# NTC.net
KiCad netlist of a schematic drawn in Altium Designer
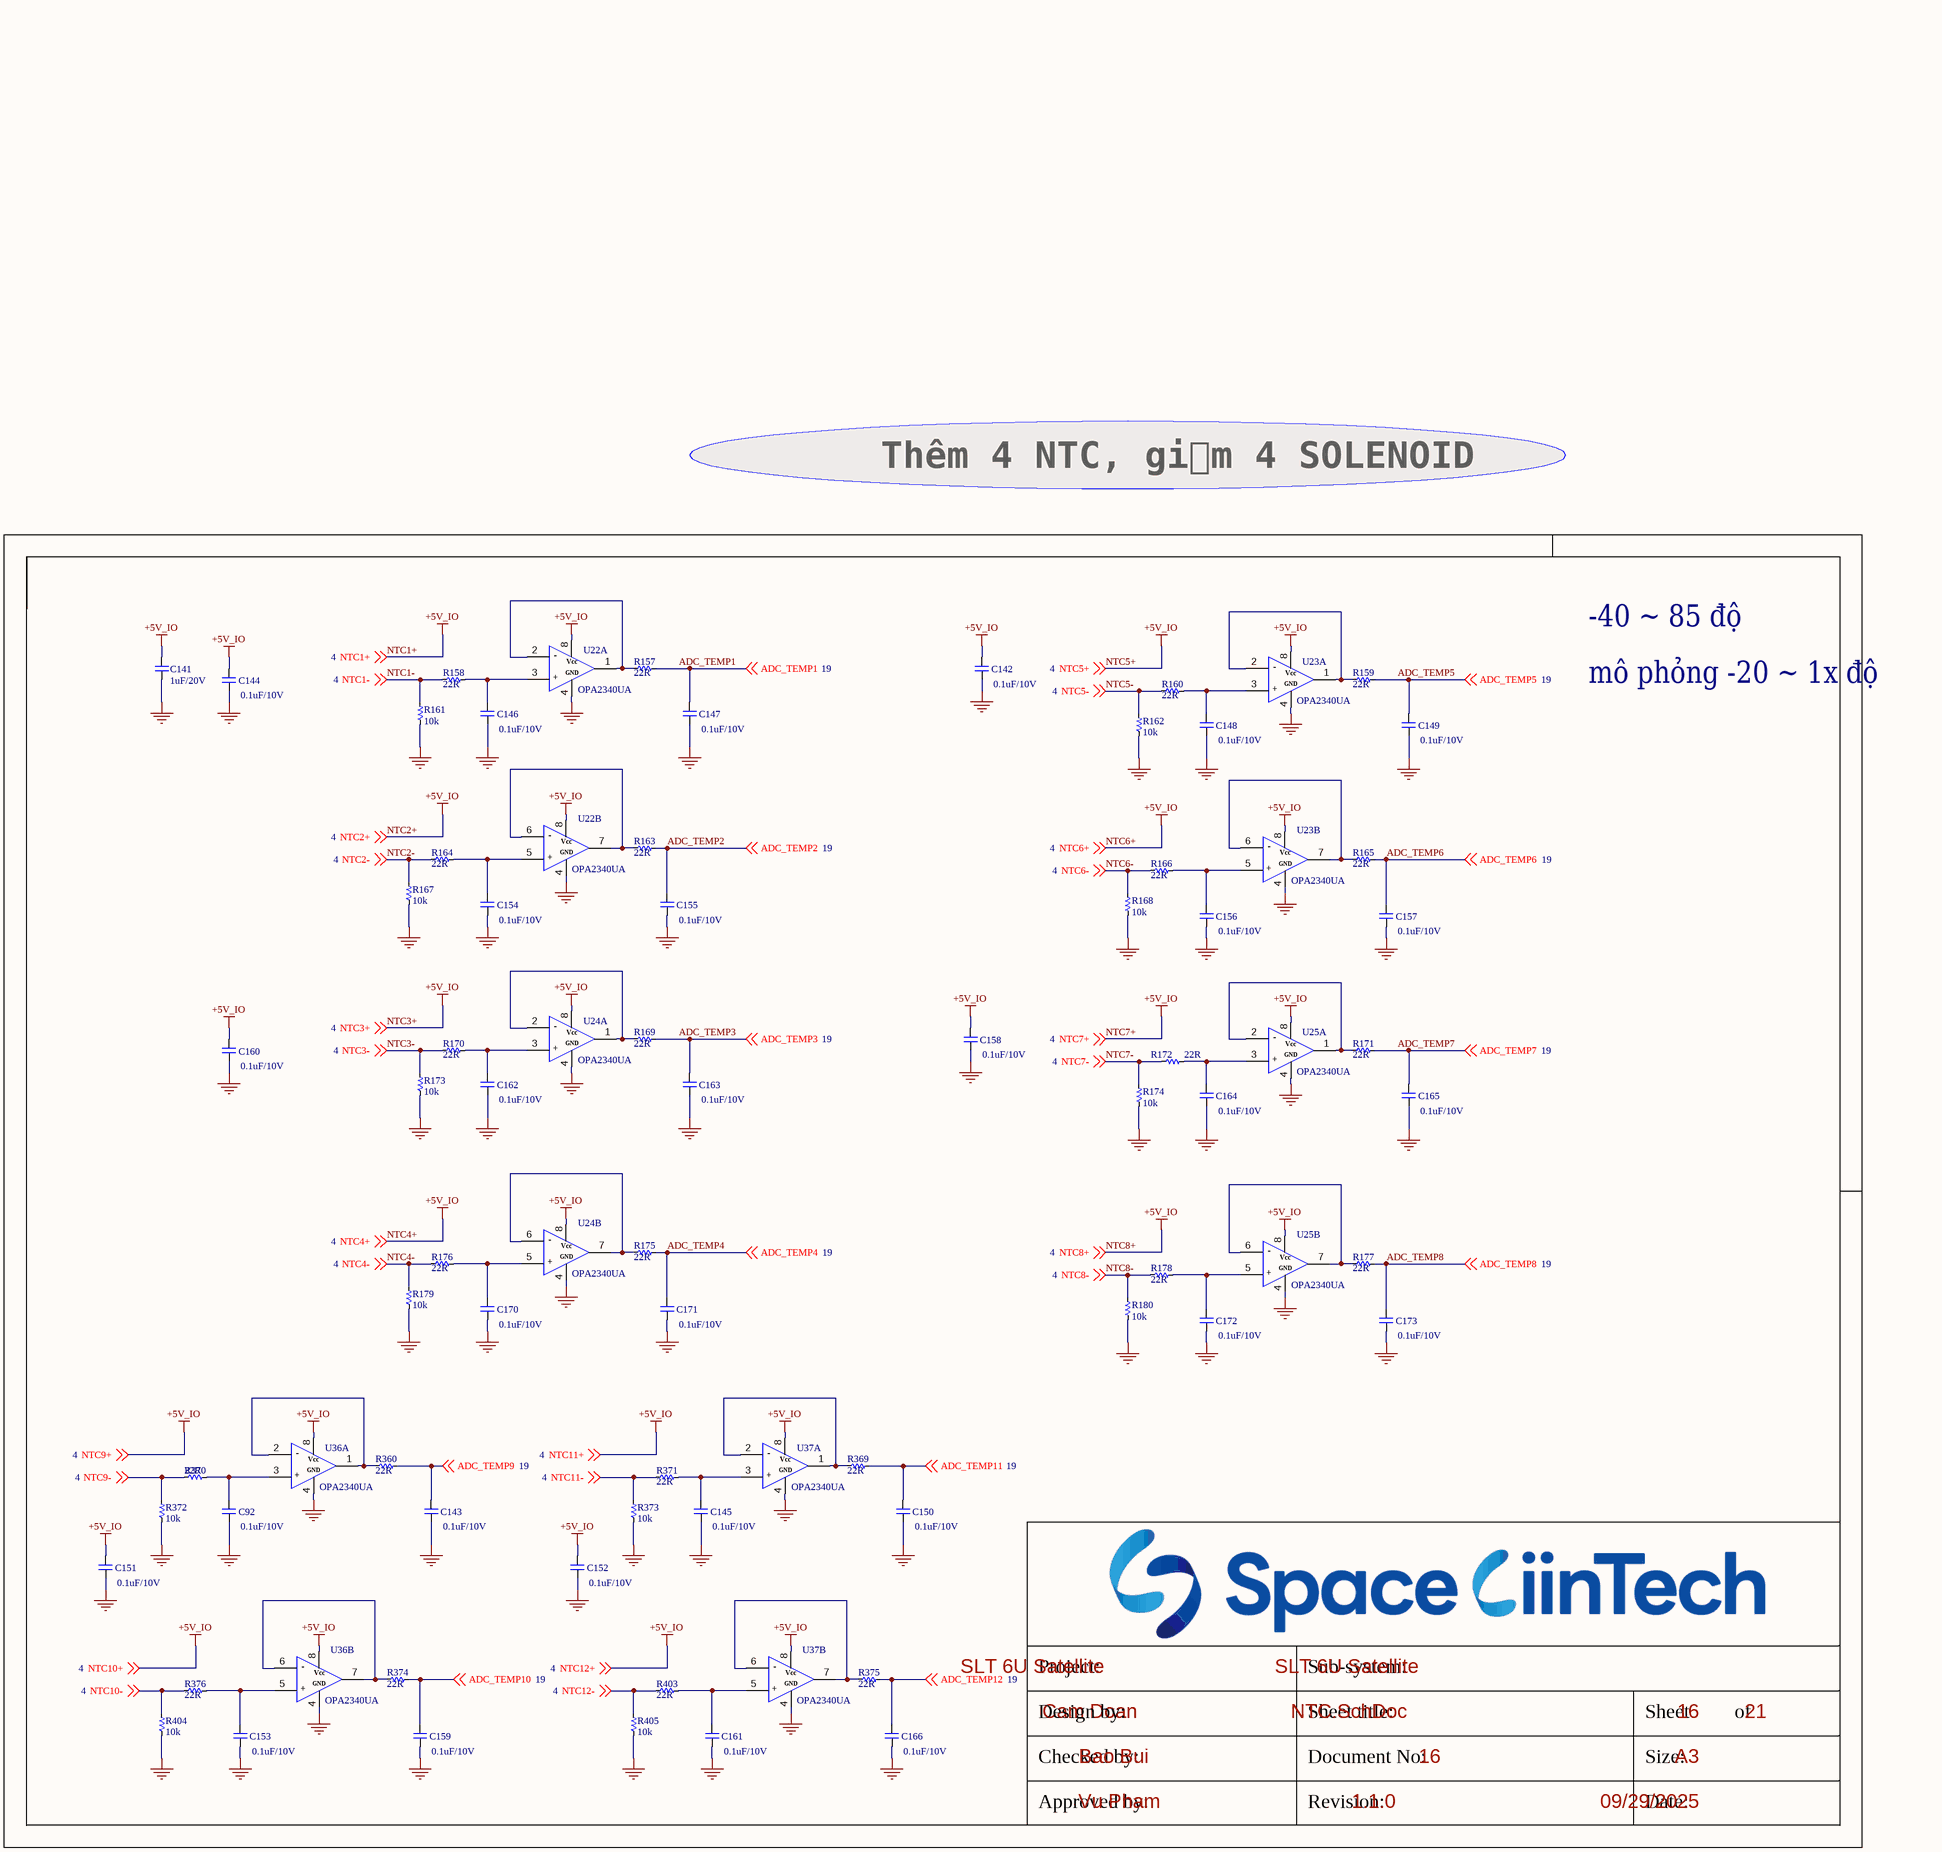
[diagram p0: NTC.SchDoc]

(export (version "E")
  (design (tool "Eeschema 10.0.6"))
  (components
    (comp (ref "C92")
      (value "0.1uF/10V")
      (footprint "CAP_C_1005X60")
      (description "CAP CHIP")
      (libsource (lib "LABLIB") (part "_CAP_C_2"))
    )
    (comp (ref "C141")
      (value "1uF/20V")
      (footprint "CAP_C_1005X60")
      (description "CAP CHIP")
      (libsource (lib "LABLIB") (part "_CAP_C_2"))
    )
    (comp (ref "C142")
      (value "0.1uF/10V")
      (footprint "CAP_C_1005X60")
      (description "CAP CHIP")
      (libsource (lib "LABLIB") (part "_CAP_C_2"))
    )
    (comp (ref "C143")
      (value "0.1uF/10V")
      (footprint "CAP_C_1005X60")
      (description "CAP CHIP")
      (libsource (lib "LABLIB") (part "_CAP_C_2"))
    )
    (comp (ref "C144")
      (value "0.1uF/10V")
      (footprint "CAP_C_1005X60")
      (description "CAP CHIP")
      (libsource (lib "LABLIB") (part "_CAP_C_2"))
    )
    (comp (ref "C145")
      (value "0.1uF/10V")
      (footprint "CAP_C_1005X60")
      (description "CAP CHIP")
      (libsource (lib "LABLIB") (part "_CAP_C_2"))
    )
    (comp (ref "C146")
      (value "0.1uF/10V")
      (footprint "CAP_C_1005X60")
      (description "CAP CHIP")
      (libsource (lib "LABLIB") (part "_CAP_C_2"))
    )
    (comp (ref "C147")
      (value "0.1uF/10V")
      (footprint "CAP_C_1005X60")
      (description "CAP CHIP")
      (libsource (lib "LABLIB") (part "_CAP_C_2"))
    )
    (comp (ref "C148")
      (value "0.1uF/10V")
      (footprint "CAP_C_1005X60")
      (description "CAP CHIP")
      (libsource (lib "LABLIB") (part "_CAP_C_2"))
    )
    (comp (ref "C149")
      (value "0.1uF/10V")
      (footprint "CAP_C_1005X60")
      (description "CAP CHIP")
      (libsource (lib "LABLIB") (part "_CAP_C_2"))
    )
    (comp (ref "C150")
      (value "0.1uF/10V")
      (footprint "CAP_C_1005X60")
      (description "CAP CHIP")
      (libsource (lib "LABLIB") (part "_CAP_C_2"))
    )
    (comp (ref "C151")
      (value "0.1uF/10V")
      (footprint "CAP_C_1005X60")
      (description "CAP CHIP")
      (libsource (lib "LABLIB") (part "_CAP_C_2"))
    )
    (comp (ref "C152")
      (value "0.1uF/10V")
      (footprint "CAP_C_1005X60")
      (description "CAP CHIP")
      (libsource (lib "LABLIB") (part "_CAP_C_2"))
    )
    (comp (ref "C153")
      (value "0.1uF/10V")
      (footprint "CAP_C_1005X60")
      (description "CAP CHIP")
      (libsource (lib "LABLIB") (part "_CAP_C_2"))
    )
    (comp (ref "C154")
      (value "0.1uF/10V")
      (footprint "CAP_C_1005X60")
      (description "CAP CHIP")
      (libsource (lib "LABLIB") (part "_CAP_C_2"))
    )
    (comp (ref "C155")
      (value "0.1uF/10V")
      (footprint "CAP_C_1005X60")
      (description "CAP CHIP")
      (libsource (lib "LABLIB") (part "_CAP_C_2"))
    )
    (comp (ref "C156")
      (value "0.1uF/10V")
      (footprint "CAP_C_1005X60")
      (description "CAP CHIP")
      (libsource (lib "LABLIB") (part "_CAP_C_2"))
    )
    (comp (ref "C157")
      (value "0.1uF/10V")
      (footprint "CAP_C_1005X60")
      (description "CAP CHIP")
      (libsource (lib "LABLIB") (part "_CAP_C_2"))
    )
    (comp (ref "C158")
      (value "0.1uF/10V")
      (footprint "CAP_C_1005X60")
      (description "CAP CHIP")
      (libsource (lib "LABLIB") (part "_CAP_C_2"))
    )
    (comp (ref "C159")
      (value "0.1uF/10V")
      (footprint "CAP_C_1005X60")
      (description "CAP CHIP")
      (libsource (lib "LABLIB") (part "_CAP_C_2"))
    )
    (comp (ref "C160")
      (value "0.1uF/10V")
      (footprint "CAP_C_1005X60")
      (description "CAP CHIP")
      (libsource (lib "LABLIB") (part "_CAP_C_2"))
    )
    (comp (ref "C161")
      (value "0.1uF/10V")
      (footprint "CAP_C_1005X60")
      (description "CAP CHIP")
      (libsource (lib "LABLIB") (part "_CAP_C_2"))
    )
    (comp (ref "C162")
      (value "0.1uF/10V")
      (footprint "CAP_C_1005X60")
      (description "CAP CHIP")
      (libsource (lib "LABLIB") (part "_CAP_C_2"))
    )
    (comp (ref "C163")
      (value "0.1uF/10V")
      (footprint "CAP_C_1005X60")
      (description "CAP CHIP")
      (libsource (lib "LABLIB") (part "_CAP_C_2"))
    )
    (comp (ref "C164")
      (value "0.1uF/10V")
      (footprint "CAP_C_1005X60")
      (description "CAP CHIP")
      (libsource (lib "LABLIB") (part "_CAP_C_2"))
    )
    (comp (ref "C165")
      (value "0.1uF/10V")
      (footprint "CAP_C_1005X60")
      (description "CAP CHIP")
      (libsource (lib "LABLIB") (part "_CAP_C_2"))
    )
    (comp (ref "C166")
      (value "0.1uF/10V")
      (footprint "CAP_C_1005X60")
      (description "CAP CHIP")
      (libsource (lib "LABLIB") (part "_CAP_C_2"))
    )
    (comp (ref "C170")
      (value "0.1uF/10V")
      (footprint "CAP_C_1005X60")
      (description "CAP CHIP")
      (libsource (lib "LABLIB") (part "_CAP_C_2"))
    )
    (comp (ref "C171")
      (value "0.1uF/10V")
      (footprint "CAP_C_1005X60")
      (description "CAP CHIP")
      (libsource (lib "LABLIB") (part "_CAP_C_2"))
    )
    (comp (ref "C172")
      (value "0.1uF/10V")
      (footprint "CAP_C_1005X60")
      (description "CAP CHIP")
      (libsource (lib "LABLIB") (part "_CAP_C_2"))
    )
    (comp (ref "C173")
      (value "0.1uF/10V")
      (footprint "CAP_C_1005X60")
      (description "CAP CHIP")
      (libsource (lib "LABLIB") (part "_CAP_C_2"))
    )
    (comp (ref "R157")
      (value "22R")
      (footprint "RES_C_1005X40")
      (description "RES")
      (libsource (lib "LABLIB") (part "_RES_B_2"))
    )
    (comp (ref "R158")
      (value "22R")
      (footprint "RES_C_1005X40")
      (description "RES")
      (libsource (lib "LABLIB") (part "_RES_B_2"))
    )
    (comp (ref "R159")
      (value "22R")
      (footprint "RES_C_1005X40")
      (description "RES")
      (libsource (lib "LABLIB") (part "_RES_B_2"))
    )
    (comp (ref "R160")
      (value "22R")
      (footprint "RES_C_1005X40")
      (description "RES")
      (libsource (lib "LABLIB") (part "_RES_B_2"))
    )
    (comp (ref "R161")
      (value "10k")
      (footprint "RES_C_1005X40")
      (description "RES")
      (libsource (lib "LABLIB") (part "_RES_B_2"))
    )
    (comp (ref "R162")
      (value "10k")
      (footprint "RES_C_1005X40")
      (description "RES")
      (libsource (lib "LABLIB") (part "_RES_B_2"))
    )
    (comp (ref "R163")
      (value "22R")
      (footprint "RES_C_1005X40")
      (description "RES")
      (libsource (lib "LABLIB") (part "_RES_B_2"))
    )
    (comp (ref "R164")
      (value "22R")
      (footprint "RES_C_1005X40")
      (description "RES")
      (libsource (lib "LABLIB") (part "_RES_B_2"))
    )
    (comp (ref "R165")
      (value "22R")
      (footprint "RES_C_1005X40")
      (description "RES")
      (libsource (lib "LABLIB") (part "_RES_B_2"))
    )
    (comp (ref "R166")
      (value "22R")
      (footprint "RES_C_1005X40")
      (description "RES")
      (libsource (lib "LABLIB") (part "_RES_B_2"))
    )
    (comp (ref "R167")
      (value "10k")
      (footprint "RES_C_1005X40")
      (description "RES")
      (libsource (lib "LABLIB") (part "_RES_B_2"))
    )
    (comp (ref "R168")
      (value "10k")
      (footprint "RES_C_1005X40")
      (description "RES")
      (libsource (lib "LABLIB") (part "_RES_B_2"))
    )
    (comp (ref "R169")
      (value "22R")
      (footprint "RES_C_1005X40")
      (description "RES")
      (libsource (lib "LABLIB") (part "_RES_B_2"))
    )
    (comp (ref "R170")
      (value "22R")
      (footprint "RES_C_1005X40")
      (description "RES")
      (libsource (lib "LABLIB") (part "_RES_B_2"))
    )
    (comp (ref "R171")
      (value "22R")
      (footprint "RES_C_1005X40")
      (description "RES")
      (libsource (lib "LABLIB") (part "_RES_B_2"))
    )
    (comp (ref "R172")
      (value "22R")
      (footprint "RES_C_1005X40")
      (description "RES")
      (libsource (lib "LABLIB") (part "_RES_B_2"))
    )
    (comp (ref "R173")
      (value "10k")
      (footprint "RES_C_1005X40")
      (description "RES")
      (libsource (lib "LABLIB") (part "_RES_B_2"))
    )
    (comp (ref "R174")
      (value "10k")
      (footprint "RES_C_1005X40")
      (description "RES")
      (libsource (lib "LABLIB") (part "_RES_B_2"))
    )
    (comp (ref "R175")
      (value "22R")
      (footprint "RES_C_1005X40")
      (description "RES")
      (libsource (lib "LABLIB") (part "_RES_B_2"))
    )
    (comp (ref "R176")
      (value "22R")
      (footprint "RES_C_1005X40")
      (description "RES")
      (libsource (lib "LABLIB") (part "_RES_B_2"))
    )
    (comp (ref "R177")
      (value "22R")
      (footprint "RES_C_1005X40")
      (description "RES")
      (libsource (lib "LABLIB") (part "_RES_B_2"))
    )
    (comp (ref "R178")
      (value "22R")
      (footprint "RES_C_1005X40")
      (description "RES")
      (libsource (lib "LABLIB") (part "_RES_B_2"))
    )
    (comp (ref "R179")
      (value "10k")
      (footprint "RES_C_1005X40")
      (description "RES")
      (libsource (lib "LABLIB") (part "_RES_B_2"))
    )
    (comp (ref "R180")
      (value "10k")
      (footprint "RES_C_1005X40")
      (description "RES")
      (libsource (lib "LABLIB") (part "_RES_B_2"))
    )
    (comp (ref "R360")
      (value "22R")
      (footprint "RES_C_1005X40")
      (description "RES")
      (libsource (lib "LABLIB") (part "_RES_B_2"))
    )
    (comp (ref "R369")
      (value "22R")
      (footprint "RES_C_1005X40")
      (description "RES")
      (libsource (lib "LABLIB") (part "_RES_B_2"))
    )
    (comp (ref "R370")
      (value "22R")
      (footprint "RES_C_1005X40")
      (description "RES")
      (libsource (lib "LABLIB") (part "_RES_B_2"))
    )
    (comp (ref "R371")
      (value "22R")
      (footprint "RES_C_1005X40")
      (description "RES")
      (libsource (lib "LABLIB") (part "_RES_B_2"))
    )
    (comp (ref "R372")
      (value "10k")
      (footprint "RES_C_1005X40")
      (description "RES")
      (libsource (lib "LABLIB") (part "_RES_B_2"))
    )
    (comp (ref "R373")
      (value "10k")
      (footprint "RES_C_1005X40")
      (description "RES")
      (libsource (lib "LABLIB") (part "_RES_B_2"))
    )
    (comp (ref "R374")
      (value "22R")
      (footprint "RES_C_1005X40")
      (description "RES")
      (libsource (lib "LABLIB") (part "_RES_B_2"))
    )
    (comp (ref "R375")
      (value "22R")
      (footprint "RES_C_1005X40")
      (description "RES")
      (libsource (lib "LABLIB") (part "_RES_B_2"))
    )
    (comp (ref "R376")
      (value "22R")
      (footprint "RES_C_1005X40")
      (description "RES")
      (libsource (lib "LABLIB") (part "_RES_B_2"))
    )
    (comp (ref "R403")
      (value "22R")
      (footprint "RES_C_1005X40")
      (description "RES")
      (libsource (lib "LABLIB") (part "_RES_B_2"))
    )
    (comp (ref "R404")
      (value "10k")
      (footprint "RES_C_1005X40")
      (description "RES")
      (libsource (lib "LABLIB") (part "_RES_B_2"))
    )
    (comp (ref "R405")
      (value "10k")
      (footprint "RES_C_1005X40")
      (description "RES")
      (libsource (lib "LABLIB") (part "_RES_B_2"))
    )
    (comp (ref "U22")
      (value "OPA2340UA")
      (footprint "SOIC127P602X173-8N")
      (libsource (lib "EXP_HW_V3") (part "OPA2340UA"))
    )
    (comp (ref "U23")
      (value "OPA2340UA")
      (footprint "SOIC127P602X173-8N")
      (libsource (lib "EXP_HW_V3") (part "OPA2340UA"))
    )
    (comp (ref "U24")
      (value "OPA2340UA")
      (footprint "SOIC127P602X173-8N")
      (libsource (lib "EXP_HW_V3") (part "OPA2340UA"))
    )
    (comp (ref "U25")
      (value "OPA2340UA")
      (footprint "SOIC127P602X173-8N")
      (libsource (lib "EXP_HW_V3") (part "OPA2340UA"))
    )
    (comp (ref "U36")
      (value "OPA2340UA")
      (footprint "SOIC127P602X173-8N")
      (libsource (lib "EXP_HW_V3") (part "OPA2340UA"))
    )
    (comp (ref "U37")
      (value "OPA2340UA")
      (footprint "SOIC127P602X173-8N")
      (libsource (lib "EXP_HW_V3") (part "OPA2340UA"))
    )
  )
  (nets
    (net (code "1") (name "+5V_IO") (class "Default")
      (node (ref "C141") (pin "2") (pinfunction "2_2") (pintype "passive"))
      (node (ref "C142") (pin "2") (pinfunction "2_2") (pintype "passive"))
      (node (ref "C144") (pin "2") (pinfunction "2_2") (pintype "passive"))
      (node (ref "C151") (pin "2") (pinfunction "2_2") (pintype "passive"))
      (node (ref "C152") (pin "2") (pinfunction "2_2") (pintype "passive"))
      (node (ref "C158") (pin "2") (pinfunction "2_2") (pintype "passive"))
      (node (ref "C160") (pin "2") (pinfunction "2_2") (pintype "passive"))
      (node (ref "U22") (pin "8") (pinfunction "8_8") (pintype "passive"))
      (node (ref "U23") (pin "8") (pinfunction "8_8") (pintype "passive"))
      (node (ref "U24") (pin "8") (pinfunction "8_8") (pintype "passive"))
      (node (ref "U25") (pin "8") (pinfunction "8_8") (pintype "passive"))
      (node (ref "U36") (pin "8") (pinfunction "8_8") (pintype "passive"))
      (node (ref "U37") (pin "8") (pinfunction "8_8") (pintype "passive"))
    )
    (net (code "2") (name "ADC_TEMP1") (class "Default")
      (node (ref "C147") (pin "2") (pinfunction "2_2") (pintype "passive"))
      (node (ref "R157") (pin "2") (pinfunction "2_2") (pintype "passive"))
    )
    (net (code "3") (name "ADC_TEMP2") (class "Default")
      (node (ref "C155") (pin "2") (pinfunction "2_2") (pintype "passive"))
      (node (ref "R163") (pin "2") (pinfunction "2_2") (pintype "passive"))
    )
    (net (code "4") (name "ADC_TEMP3") (class "Default")
      (node (ref "C163") (pin "2") (pinfunction "2_2") (pintype "passive"))
      (node (ref "R169") (pin "2") (pinfunction "2_2") (pintype "passive"))
    )
    (net (code "5") (name "ADC_TEMP4") (class "Default")
      (node (ref "C171") (pin "2") (pinfunction "2_2") (pintype "passive"))
      (node (ref "R175") (pin "2") (pinfunction "2_2") (pintype "passive"))
    )
    (net (code "6") (name "ADC_TEMP5") (class "Default")
      (node (ref "C149") (pin "2") (pinfunction "2_2") (pintype "passive"))
      (node (ref "R159") (pin "2") (pinfunction "2_2") (pintype "passive"))
    )
    (net (code "7") (name "ADC_TEMP6") (class "Default")
      (node (ref "C157") (pin "2") (pinfunction "2_2") (pintype "passive"))
      (node (ref "R165") (pin "2") (pinfunction "2_2") (pintype "passive"))
    )
    (net (code "8") (name "ADC_TEMP7") (class "Default")
      (node (ref "C165") (pin "2") (pinfunction "2_2") (pintype "passive"))
      (node (ref "R171") (pin "2") (pinfunction "2_2") (pintype "passive"))
    )
    (net (code "9") (name "ADC_TEMP8") (class "Default")
      (node (ref "C173") (pin "2") (pinfunction "2_2") (pintype "passive"))
      (node (ref "R177") (pin "2") (pinfunction "2_2") (pintype "passive"))
    )
    (net (code "10") (name "ADC_TEMP9") (class "Default")
      (node (ref "C143") (pin "2") (pinfunction "2_2") (pintype "passive"))
      (node (ref "R360") (pin "2") (pinfunction "2_2") (pintype "passive"))
    )
    (net (code "11") (name "ADC_TEMP10") (class "Default")
      (node (ref "C159") (pin "2") (pinfunction "2_2") (pintype "passive"))
      (node (ref "R374") (pin "2") (pinfunction "2_2") (pintype "passive"))
    )
    (net (code "12") (name "ADC_TEMP11") (class "Default")
      (node (ref "C150") (pin "2") (pinfunction "2_2") (pintype "passive"))
      (node (ref "R369") (pin "2") (pinfunction "2_2") (pintype "passive"))
    )
    (net (code "13") (name "ADC_TEMP12") (class "Default")
      (node (ref "C166") (pin "2") (pinfunction "2_2") (pintype "passive"))
      (node (ref "R375") (pin "2") (pinfunction "2_2") (pintype "passive"))
    )
    (net (code "14") (name "GND") (class "Default")
      (node (ref "C141") (pin "1") (pinfunction "1_1") (pintype "passive"))
      (node (ref "C142") (pin "1") (pinfunction "1_1") (pintype "passive"))
      (node (ref "C143") (pin "1") (pinfunction "1_1") (pintype "passive"))
      (node (ref "C144") (pin "1") (pinfunction "1_1") (pintype "passive"))
      (node (ref "C145") (pin "1") (pinfunction "1_1") (pintype "passive"))
      (node (ref "C146") (pin "1") (pinfunction "1_1") (pintype "passive"))
      (node (ref "C147") (pin "1") (pinfunction "1_1") (pintype "passive"))
      (node (ref "C148") (pin "1") (pinfunction "1_1") (pintype "passive"))
      (node (ref "C149") (pin "1") (pinfunction "1_1") (pintype "passive"))
      (node (ref "C150") (pin "1") (pinfunction "1_1") (pintype "passive"))
      (node (ref "C151") (pin "1") (pinfunction "1_1") (pintype "passive"))
      (node (ref "C152") (pin "1") (pinfunction "1_1") (pintype "passive"))
      (node (ref "C153") (pin "1") (pinfunction "1_1") (pintype "passive"))
      (node (ref "C154") (pin "1") (pinfunction "1_1") (pintype "passive"))
      (node (ref "C155") (pin "1") (pinfunction "1_1") (pintype "passive"))
      (node (ref "C156") (pin "1") (pinfunction "1_1") (pintype "passive"))
      (node (ref "C157") (pin "1") (pinfunction "1_1") (pintype "passive"))
      (node (ref "C158") (pin "1") (pinfunction "1_1") (pintype "passive"))
      (node (ref "C159") (pin "1") (pinfunction "1_1") (pintype "passive"))
      (node (ref "C160") (pin "1") (pinfunction "1_1") (pintype "passive"))
      (node (ref "C161") (pin "1") (pinfunction "1_1") (pintype "passive"))
      (node (ref "C162") (pin "1") (pinfunction "1_1") (pintype "passive"))
      (node (ref "C163") (pin "1") (pinfunction "1_1") (pintype "passive"))
      (node (ref "C164") (pin "1") (pinfunction "1_1") (pintype "passive"))
      (node (ref "C165") (pin "1") (pinfunction "1_1") (pintype "passive"))
      (node (ref "C166") (pin "1") (pinfunction "1_1") (pintype "passive"))
      (node (ref "C170") (pin "1") (pinfunction "1_1") (pintype "passive"))
      (node (ref "C171") (pin "1") (pinfunction "1_1") (pintype "passive"))
      (node (ref "C172") (pin "1") (pinfunction "1_1") (pintype "passive"))
      (node (ref "C173") (pin "1") (pinfunction "1_1") (pintype "passive"))
      (node (ref "C92") (pin "1") (pinfunction "1_1") (pintype "passive"))
      (node (ref "R161") (pin "1") (pinfunction "1_1") (pintype "passive"))
      (node (ref "R162") (pin "1") (pinfunction "1_1") (pintype "passive"))
      (node (ref "R167") (pin "1") (pinfunction "1_1") (pintype "passive"))
      (node (ref "R168") (pin "1") (pinfunction "1_1") (pintype "passive"))
      (node (ref "R173") (pin "1") (pinfunction "1_1") (pintype "passive"))
      (node (ref "R174") (pin "1") (pinfunction "1_1") (pintype "passive"))
      (node (ref "R179") (pin "1") (pinfunction "1_1") (pintype "passive"))
      (node (ref "R180") (pin "1") (pinfunction "1_1") (pintype "passive"))
      (node (ref "R372") (pin "1") (pinfunction "1_1") (pintype "passive"))
      (node (ref "R373") (pin "1") (pinfunction "1_1") (pintype "passive"))
      (node (ref "R404") (pin "1") (pinfunction "1_1") (pintype "passive"))
      (node (ref "R405") (pin "1") (pinfunction "1_1") (pintype "passive"))
      (node (ref "U22") (pin "4") (pinfunction "4_4") (pintype "passive"))
      (node (ref "U23") (pin "4") (pinfunction "4_4") (pintype "passive"))
      (node (ref "U24") (pin "4") (pinfunction "4_4") (pintype "passive"))
      (node (ref "U25") (pin "4") (pinfunction "4_4") (pintype "passive"))
      (node (ref "U36") (pin "4") (pinfunction "4_4") (pintype "passive"))
      (node (ref "U37") (pin "4") (pinfunction "4_4") (pintype "passive"))
    )
    (net (code "15") (name "NTC1-") (class "Default")
      (node (ref "R158") (pin "1") (pinfunction "1_1") (pintype "passive"))
      (node (ref "R161") (pin "2") (pinfunction "2_2") (pintype "passive"))
    )
    (net (code "16") (name "NTC2-") (class "Default")
      (node (ref "R164") (pin "1") (pinfunction "1_1") (pintype "passive"))
      (node (ref "R167") (pin "2") (pinfunction "2_2") (pintype "passive"))
    )
    (net (code "17") (name "NTC3-") (class "Default")
      (node (ref "R170") (pin "1") (pinfunction "1_1") (pintype "passive"))
      (node (ref "R173") (pin "2") (pinfunction "2_2") (pintype "passive"))
    )
    (net (code "18") (name "NTC4-") (class "Default")
      (node (ref "R176") (pin "1") (pinfunction "1_1") (pintype "passive"))
      (node (ref "R179") (pin "2") (pinfunction "2_2") (pintype "passive"))
    )
    (net (code "19") (name "NTC5-") (class "Default")
      (node (ref "R160") (pin "1") (pinfunction "1_1") (pintype "passive"))
      (node (ref "R162") (pin "2") (pinfunction "2_2") (pintype "passive"))
    )
    (net (code "20") (name "NTC6-") (class "Default")
      (node (ref "R166") (pin "1") (pinfunction "1_1") (pintype "passive"))
      (node (ref "R168") (pin "2") (pinfunction "2_2") (pintype "passive"))
    )
    (net (code "21") (name "NTC7-") (class "Default")
      (node (ref "R172") (pin "1") (pinfunction "1_1") (pintype "passive"))
      (node (ref "R174") (pin "2") (pinfunction "2_2") (pintype "passive"))
    )
    (net (code "22") (name "NTC8-") (class "Default")
      (node (ref "R178") (pin "1") (pinfunction "1_1") (pintype "passive"))
      (node (ref "R180") (pin "2") (pinfunction "2_2") (pintype "passive"))
    )
    (net (code "23") (name "NTC9-") (class "Default")
      (node (ref "R370") (pin "1") (pinfunction "1_1") (pintype "passive"))
      (node (ref "R372") (pin "2") (pinfunction "2_2") (pintype "passive"))
    )
    (net (code "24") (name "NTC10-") (class "Default")
      (node (ref "R376") (pin "1") (pinfunction "1_1") (pintype "passive"))
      (node (ref "R404") (pin "2") (pinfunction "2_2") (pintype "passive"))
    )
    (net (code "25") (name "NTC11-") (class "Default")
      (node (ref "R371") (pin "1") (pinfunction "1_1") (pintype "passive"))
      (node (ref "R373") (pin "2") (pinfunction "2_2") (pintype "passive"))
    )
    (net (code "26") (name "NTC12-") (class "Default")
      (node (ref "R403") (pin "1") (pinfunction "1_1") (pintype "passive"))
      (node (ref "R405") (pin "2") (pinfunction "2_2") (pintype "passive"))
    )
    (net (code "27") (name "Net-(C92-Pad2)") (class "Default")
      (node (ref "C92") (pin "2") (pinfunction "2_2") (pintype "passive"))
      (node (ref "R370") (pin "2") (pinfunction "2_2") (pintype "passive"))
      (node (ref "U36") (pin "3") (pinfunction "3_3") (pintype "passive"))
    )
    (net (code "28") (name "Net-(C145-Pad2)") (class "Default")
      (node (ref "C145") (pin "2") (pinfunction "2_2") (pintype "passive"))
      (node (ref "R371") (pin "2") (pinfunction "2_2") (pintype "passive"))
      (node (ref "U37") (pin "3") (pinfunction "3_3") (pintype "passive"))
    )
    (net (code "29") (name "Net-(C146-Pad2)") (class "Default")
      (node (ref "C146") (pin "2") (pinfunction "2_2") (pintype "passive"))
      (node (ref "R158") (pin "2") (pinfunction "2_2") (pintype "passive"))
      (node (ref "U22") (pin "3") (pinfunction "3_3") (pintype "passive"))
    )
    (net (code "30") (name "Net-(C148-Pad2)") (class "Default")
      (node (ref "C148") (pin "2") (pinfunction "2_2") (pintype "passive"))
      (node (ref "R160") (pin "2") (pinfunction "2_2") (pintype "passive"))
      (node (ref "U23") (pin "3") (pinfunction "3_3") (pintype "passive"))
    )
    (net (code "31") (name "Net-(C153-Pad2)") (class "Default")
      (node (ref "C153") (pin "2") (pinfunction "2_2") (pintype "passive"))
      (node (ref "R376") (pin "2") (pinfunction "2_2") (pintype "passive"))
      (node (ref "U36") (pin "5") (pinfunction "5_5") (pintype "passive"))
    )
    (net (code "32") (name "Net-(C154-Pad2)") (class "Default")
      (node (ref "C154") (pin "2") (pinfunction "2_2") (pintype "passive"))
      (node (ref "R164") (pin "2") (pinfunction "2_2") (pintype "passive"))
      (node (ref "U22") (pin "5") (pinfunction "5_5") (pintype "passive"))
    )
    (net (code "33") (name "Net-(C156-Pad2)") (class "Default")
      (node (ref "C156") (pin "2") (pinfunction "2_2") (pintype "passive"))
      (node (ref "R166") (pin "2") (pinfunction "2_2") (pintype "passive"))
      (node (ref "U23") (pin "5") (pinfunction "5_5") (pintype "passive"))
    )
    (net (code "34") (name "Net-(C161-Pad2)") (class "Default")
      (node (ref "C161") (pin "2") (pinfunction "2_2") (pintype "passive"))
      (node (ref "R403") (pin "2") (pinfunction "2_2") (pintype "passive"))
      (node (ref "U37") (pin "5") (pinfunction "5_5") (pintype "passive"))
    )
    (net (code "35") (name "Net-(C162-Pad2)") (class "Default")
      (node (ref "C162") (pin "2") (pinfunction "2_2") (pintype "passive"))
      (node (ref "R170") (pin "2") (pinfunction "2_2") (pintype "passive"))
      (node (ref "U24") (pin "3") (pinfunction "3_3") (pintype "passive"))
    )
    (net (code "36") (name "Net-(C164-Pad2)") (class "Default")
      (node (ref "C164") (pin "2") (pinfunction "2_2") (pintype "passive"))
      (node (ref "R172") (pin "2") (pinfunction "2_2") (pintype "passive"))
      (node (ref "U25") (pin "3") (pinfunction "3_3") (pintype "passive"))
    )
    (net (code "37") (name "Net-(C170-Pad2)") (class "Default")
      (node (ref "C170") (pin "2") (pinfunction "2_2") (pintype "passive"))
      (node (ref "R176") (pin "2") (pinfunction "2_2") (pintype "passive"))
      (node (ref "U24") (pin "5") (pinfunction "5_5") (pintype "passive"))
    )
    (net (code "38") (name "Net-(C172-Pad2)") (class "Default")
      (node (ref "C172") (pin "2") (pinfunction "2_2") (pintype "passive"))
      (node (ref "R178") (pin "2") (pinfunction "2_2") (pintype "passive"))
      (node (ref "U25") (pin "5") (pinfunction "5_5") (pintype "passive"))
    )
    (net (code "39") (name "Net-(R157-Pad1)") (class "Default")
      (node (ref "R157") (pin "1") (pinfunction "1_1") (pintype "passive"))
      (node (ref "U22") (pin "1") (pinfunction "1_1") (pintype "passive"))
      (node (ref "U22") (pin "2") (pinfunction "2_2") (pintype "passive"))
    )
    (net (code "40") (name "Net-(R159-Pad1)") (class "Default")
      (node (ref "R159") (pin "1") (pinfunction "1_1") (pintype "passive"))
      (node (ref "U23") (pin "1") (pinfunction "1_1") (pintype "passive"))
      (node (ref "U23") (pin "2") (pinfunction "2_2") (pintype "passive"))
    )
    (net (code "41") (name "Net-(R163-Pad1)") (class "Default")
      (node (ref "R163") (pin "1") (pinfunction "1_1") (pintype "passive"))
      (node (ref "U22") (pin "6") (pinfunction "6_6") (pintype "passive"))
      (node (ref "U22") (pin "7") (pinfunction "7_7") (pintype "passive"))
    )
    (net (code "42") (name "Net-(R165-Pad1)") (class "Default")
      (node (ref "R165") (pin "1") (pinfunction "1_1") (pintype "passive"))
      (node (ref "U23") (pin "6") (pinfunction "6_6") (pintype "passive"))
      (node (ref "U23") (pin "7") (pinfunction "7_7") (pintype "passive"))
    )
    (net (code "43") (name "Net-(R169-Pad1)") (class "Default")
      (node (ref "R169") (pin "1") (pinfunction "1_1") (pintype "passive"))
      (node (ref "U24") (pin "1") (pinfunction "1_1") (pintype "passive"))
      (node (ref "U24") (pin "2") (pinfunction "2_2") (pintype "passive"))
    )
    (net (code "44") (name "Net-(R171-Pad1)") (class "Default")
      (node (ref "R171") (pin "1") (pinfunction "1_1") (pintype "passive"))
      (node (ref "U25") (pin "1") (pinfunction "1_1") (pintype "passive"))
      (node (ref "U25") (pin "2") (pinfunction "2_2") (pintype "passive"))
    )
    (net (code "45") (name "Net-(R175-Pad1)") (class "Default")
      (node (ref "R175") (pin "1") (pinfunction "1_1") (pintype "passive"))
      (node (ref "U24") (pin "6") (pinfunction "6_6") (pintype "passive"))
      (node (ref "U24") (pin "7") (pinfunction "7_7") (pintype "passive"))
    )
    (net (code "46") (name "Net-(R177-Pad1)") (class "Default")
      (node (ref "R177") (pin "1") (pinfunction "1_1") (pintype "passive"))
      (node (ref "U25") (pin "6") (pinfunction "6_6") (pintype "passive"))
      (node (ref "U25") (pin "7") (pinfunction "7_7") (pintype "passive"))
    )
    (net (code "47") (name "Net-(R360-Pad1)") (class "Default")
      (node (ref "R360") (pin "1") (pinfunction "1_1") (pintype "passive"))
      (node (ref "U36") (pin "1") (pinfunction "1_1") (pintype "passive"))
      (node (ref "U36") (pin "2") (pinfunction "2_2") (pintype "passive"))
    )
    (net (code "48") (name "Net-(R369-Pad1)") (class "Default")
      (node (ref "R369") (pin "1") (pinfunction "1_1") (pintype "passive"))
      (node (ref "U37") (pin "1") (pinfunction "1_1") (pintype "passive"))
      (node (ref "U37") (pin "2") (pinfunction "2_2") (pintype "passive"))
    )
    (net (code "49") (name "Net-(R374-Pad1)") (class "Default")
      (node (ref "R374") (pin "1") (pinfunction "1_1") (pintype "passive"))
      (node (ref "U36") (pin "6") (pinfunction "6_6") (pintype "passive"))
      (node (ref "U36") (pin "7") (pinfunction "7_7") (pintype "passive"))
    )
    (net (code "50") (name "Net-(R375-Pad1)") (class "Default")
      (node (ref "R375") (pin "1") (pinfunction "1_1") (pintype "passive"))
      (node (ref "U37") (pin "6") (pinfunction "6_6") (pintype "passive"))
      (node (ref "U37") (pin "7") (pinfunction "7_7") (pintype "passive"))
    )
  )
)
